# DLY-056-13V_3A-KP212.net
KiCad netlist of a schematic drawn in Altium Designer
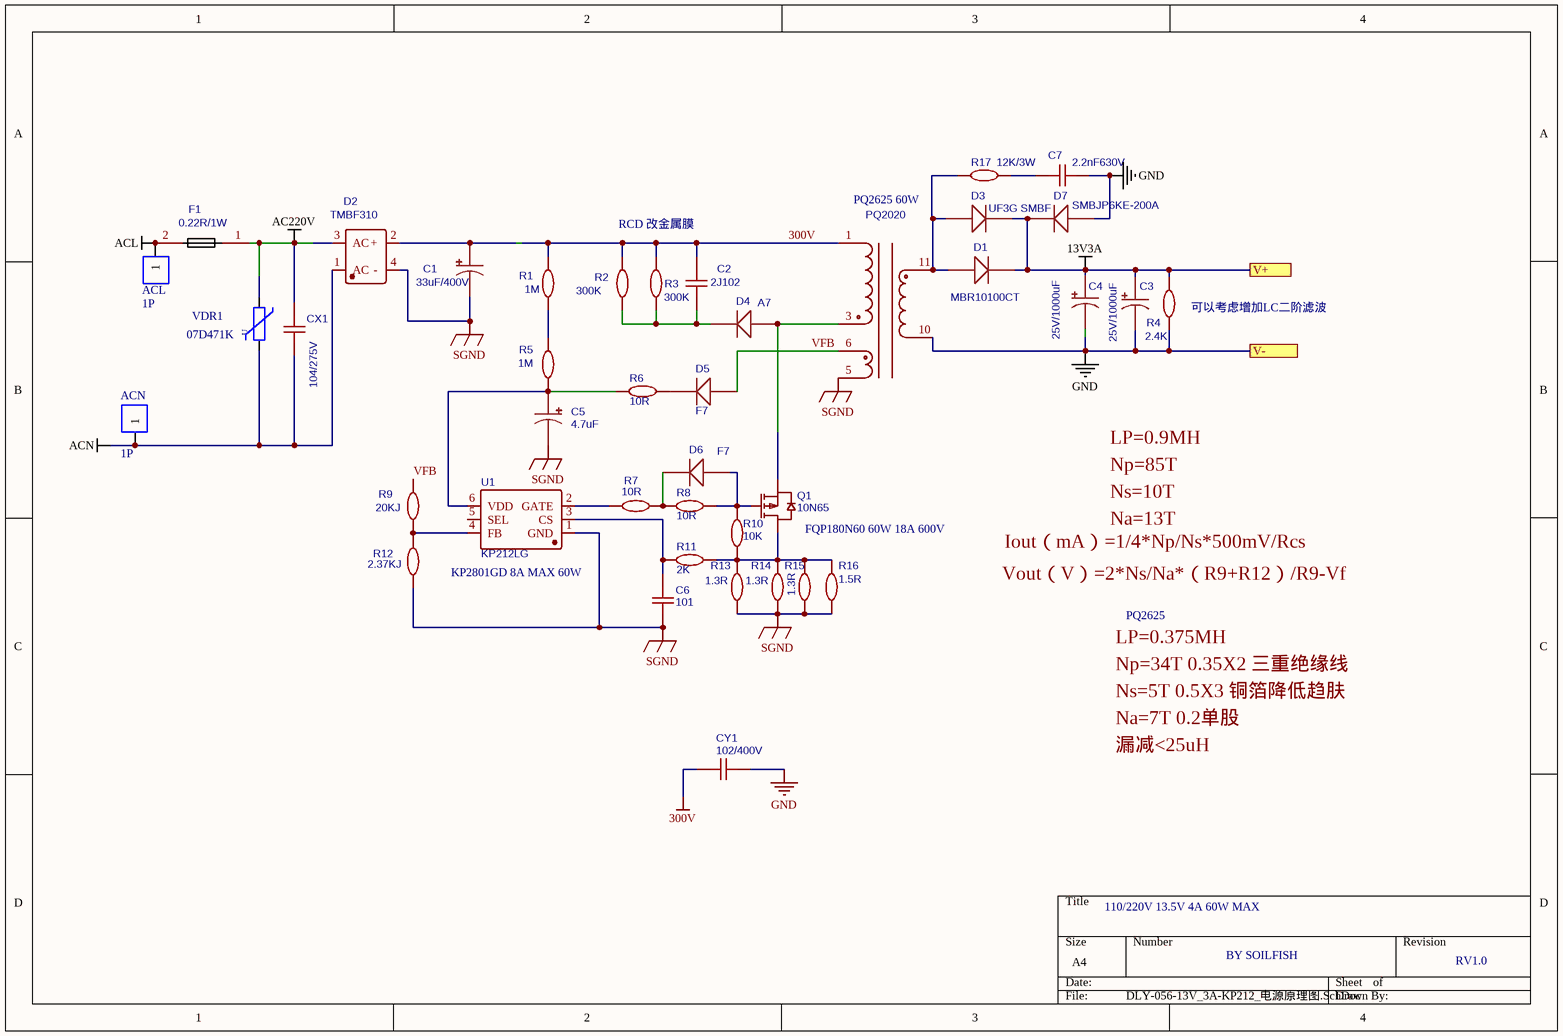
[diagram p0: DLY-056-13V_3A-KP212_电源原理图.SchDoc]

(export (version "E")
  (design (tool "Eeschema 10.0.6"))
  (components
    (comp (ref "ACL")
      (value "1P")
      (footprint "TEST3.0_top")
      (libsource (lib "KENNED 原理图标准封装-2023-9-7") (part "1P"))
    )
    (comp (ref "ACN")
      (value "1P")
      (footprint "TEST3.0_top")
      (libsource (lib "KENNED 原理图标准封装-2023-9-7") (part "1P"))
    )
    (comp (ref "C1")
      (value "33uF/400V")
      (footprint "DIP-EC5.0X12.5X20-A")
      (fields
        (field (name "BOM_SUPPLIER PART") "C503210")
        (field (name "BOM_MANUFACTURER PART") "01EC0069SHG4.7uF400V")
        (field (name "CONTRIBUTOR") "LCSC")
      )
      (libsource (lib "altium-import") (part "root_0_4.7uF_"))
    )
    (comp (ref "C2")
      (value "2J102")
      (footprint "SMT-1206C")
      (fields
        (field (name "BOM_MANUFACTURER PART") "CL10B104KA8NNNC")
        (field (name "BOM_SUPPLIER PART") "C1590")
      )
      (libsource (lib "altium-import") (part "root_1_102/400V_"))
    )
    (comp (ref "C3")
      (value "25V/1000uF")
      (footprint "DIP-EC3.5X8X11.5-A")
      (fields
        (field (name "BOM_SUPPLIER PART") "C503210")
        (field (name "BOM_MANUFACTURER PART") "01EC0069SHG4.7uF400V")
        (field (name "CONTRIBUTOR") "LCSC")
      )
      (libsource (lib "altium-import") (part "root_0_680uF_"))
    )
    (comp (ref "C4")
      (value "25V/1000uF")
      (footprint "DIP-EC3.5X8X11.5-A")
      (fields
        (field (name "BOM_SUPPLIER PART") "C503210")
        (field (name "BOM_MANUFACTURER PART") "01EC0069SHG4.7uF400V")
        (field (name "CONTRIBUTOR") "LCSC")
      )
      (libsource (lib "altium-import") (part "root_0_680uF_"))
    )
    (comp (ref "C5")
      (value "4.7uF")
      (footprint "DIP-EC2.5X5X11")
      (fields
        (field (name "BOM_SUPPLIER PART") "C503210")
        (field (name "BOM_MANUFACTURER PART") "01EC0069SHG4.7uF400V")
        (field (name "CONTRIBUTOR") "LCSC")
      )
      (libsource (lib "altium-import") (part "root_0_mirrored_4.7uF_"))
    )
    (comp (ref "C6")
      (value "101")
      (footprint "0805_C")
      (fields
        (field (name "BOM_MANUFACTURER PART") "CL10B104KA8NNNC")
        (field (name "BOM_SUPPLIER PART") "C1590")
      )
      (libsource (lib "altium-import") (part "root_1_102/400V_"))
    )
    (comp (ref "C7")
      (value "2.2nF630V")
      (footprint "SMT-1206C")
      (fields
        (field (name "BOM_MANUFACTURER PART") "CL10B104KA8NNNC")
        (field (name "BOM_SUPPLIER PART") "C1590")
      )
      (libsource (lib "altium-import") (part "root_2_102/400V_"))
    )
    (comp (ref "CX1")
      (value "104/275V")
      (footprint "AII-C10X5-5")
      (fields
        (field (name "BOM_MANUFACTURER PART") "CL10B104KA8NNNC")
        (field (name "BOM_SUPPLIER PART") "C1590")
      )
      (libsource (lib "altium-import") (part "root_1_102/400V_"))
    )
    (comp (ref "CY1")
      (value "102/400V")
      (footprint "MI-CY11.5X4.5-10")
      (fields
        (field (name "BOM_MANUFACTURER PART") "CL10B104KA8NNNC")
        (field (name "BOM_SUPPLIER PART") "C1590")
      )
      (libsource (lib "altium-import") (part "root_2_471/100V_"))
    )
    (comp (ref "D1")
      (value "MBR10100CT")
      (footprint "SMT-TO252锡膏-二极管")
      (fields
        (field (name "BOM_MANUFACTURER PART") "1N4148WSF-7")
        (field (name "BOM_SUPPLIER PART") "C119617")
        (field (name "CONTRIBUTOR") "LCSC")
      )
      (libsource (lib "altium-import") (part "root_2_A7_"))
    )
    (comp (ref "D2")
      (value "TMBF310")
      (footprint "DBS")
      (fields
        (field (name "BOM_SUPPLIER PART") "C347350")
        (field (name "BOM_MANUFACTURER PART") "MB10F(0.8A)")
        (field (name "CONTRIBUTOR") "LCSC")
      )
      (libsource (lib "altium-import") (part "root_1_MB10F(0.8A)_"))
    )
    (comp (ref "D3")
      (value "UF3G SMBF")
      (footprint "SMT-TO252锡膏-二极管")
      (fields
        (field (name "BOM_MANUFACTURER PART") "1N4148WSF-7")
        (field (name "BOM_SUPPLIER PART") "C119617")
        (field (name "CONTRIBUTOR") "LCSC")
      )
      (libsource (lib "altium-import") (part "root_2_A7_"))
    )
    (comp (ref "D4")
      (value "A7")
      (footprint "SMA(DO-214AC)_S1")
      (fields
        (field (name "BOM_MANUFACTURER PART") "1N4148WSF-7")
        (field (name "BOM_SUPPLIER PART") "C119617")
        (field (name "CONTRIBUTOR") "LCSC")
      )
      (libsource (lib "altium-import") (part "root_0_A7_"))
    )
    (comp (ref "D5")
      (value "F7")
      (footprint "SMT-SOD123锡膏")
      (fields
        (field (name "BOM_MANUFACTURER PART") "1N4148WSF-7")
        (field (name "BOM_SUPPLIER PART") "C119617")
        (field (name "CONTRIBUTOR") "LCSC")
      )
      (libsource (lib "altium-import") (part "root_2_mirrored_A7_"))
    )
    (comp (ref "D6")
      (value "F7")
      (footprint "SMT-SOD123锡膏")
      (fields
        (field (name "BOM_MANUFACTURER PART") "1N4148WSF-7")
        (field (name "BOM_SUPPLIER PART") "C119617")
        (field (name "CONTRIBUTOR") "LCSC")
      )
      (libsource (lib "altium-import") (part "root_0_A7_"))
    )
    (comp (ref "D7")
      (value "SMBJP6KE-200A")
      (footprint "SMT-TO252锡膏-二极管")
      (fields
        (field (name "BOM_MANUFACTURER PART") "1N4148WSF-7")
        (field (name "BOM_SUPPLIER PART") "C119617")
        (field (name "CONTRIBUTOR") "LCSC")
      )
      (libsource (lib "altium-import") (part "root_0_A7_"))
    )
    (comp (ref "F1")
      (value "0.22R/1W")
      (footprint "AI-R11X4-15")
      (fields (field (name "BOM_SUPPLIER PART") "C36902"))
      (libsource (lib "altium-import") (part "root_2_2A/250V_"))
    )
    (comp (ref "Q1")
      (value "10N65")
      (footprint "TO-220带散热片-MOS")
      (fields
        (field (name "BOM_SUPPLIER PART") "C239055")
        (field (name "BOM_MANUFACTURER PART") "3401")
        (field (name "CONTRIBUTOR") "LCSC")
      )
      (libsource (lib "altium-import") (part "root_2_3401_"))
    )
    (comp (ref "R1")
      (value "1M")
      (footprint "1206_r")
      (fields
        (field (name "BOM_SUPPLIER PART") "C270129")
        (field (name "BOM_MANUFACTURER PART") "RMC04024.7K1%N")
        (field (name "CONTRIBUTOR") "LCSC")
      )
      (libsource (lib "altium-import") (part "root_1_300K_"))
    )
    (comp (ref "R2")
      (value "300K")
      (footprint "1206_r")
      (fields
        (field (name "BOM_SUPPLIER PART") "C270129")
        (field (name "BOM_MANUFACTURER PART") "RMC04024.7K1%N")
        (field (name "CONTRIBUTOR") "LCSC")
      )
      (libsource (lib "altium-import") (part "root_1_120R_"))
    )
    (comp (ref "R3")
      (value "300K")
      (footprint "1206_r")
      (fields
        (field (name "BOM_SUPPLIER PART") "C270129")
        (field (name "BOM_MANUFACTURER PART") "RMC04024.7K1%N")
        (field (name "CONTRIBUTOR") "LCSC")
      )
      (libsource (lib "altium-import") (part "root_1_300K_"))
    )
    (comp (ref "R4")
      (value "2.4K")
      (footprint "0805_r")
      (fields
        (field (name "BOM_SUPPLIER PART") "C270129")
        (field (name "BOM_MANUFACTURER PART") "RMC04024.7K1%N")
        (field (name "CONTRIBUTOR") "LCSC")
      )
      (libsource (lib "altium-import") (part "root_3_6.8K_"))
    )
    (comp (ref "R5")
      (value "1M")
      (footprint "1206_r")
      (fields
        (field (name "BOM_SUPPLIER PART") "C270129")
        (field (name "BOM_MANUFACTURER PART") "RMC04024.7K1%N")
        (field (name "CONTRIBUTOR") "LCSC")
      )
      (libsource (lib "altium-import") (part "root_1_300K_"))
    )
    (comp (ref "R6")
      (value "10R")
      (footprint "0805_r")
      (fields
        (field (name "BOM_SUPPLIER PART") "C270129")
        (field (name "BOM_MANUFACTURER PART") "RMC04024.7K1%N")
        (field (name "CONTRIBUTOR") "LCSC")
      )
      (libsource (lib "altium-import") (part "root_0_mirrored_300K_"))
    )
    (comp (ref "R7")
      (value "10R")
      (footprint "0805_r")
      (fields
        (field (name "BOM_SUPPLIER PART") "C270129")
        (field (name "BOM_MANUFACTURER PART") "RMC04024.7K1%N")
        (field (name "CONTRIBUTOR") "LCSC")
      )
      (libsource (lib "altium-import") (part "root_2_300K_"))
    )
    (comp (ref "R8")
      (value "10R")
      (footprint "0805_r")
      (fields
        (field (name "BOM_SUPPLIER PART") "C270129")
        (field (name "BOM_MANUFACTURER PART") "RMC04024.7K1%N")
        (field (name "CONTRIBUTOR") "LCSC")
      )
      (libsource (lib "altium-import") (part "root_2_300K_"))
    )
    (comp (ref "R9")
      (value "20KJ")
      (footprint "0805_r")
      (fields
        (field (name "BOM_SUPPLIER PART") "C270129")
        (field (name "BOM_MANUFACTURER PART") "RMC04024.7K1%N")
        (field (name "CONTRIBUTOR") "LCSC")
      )
      (libsource (lib "altium-import") (part "root_3_300K_"))
    )
    (comp (ref "R10")
      (value "10K")
      (footprint "0805_r")
      (fields
        (field (name "BOM_SUPPLIER PART") "C270129")
        (field (name "BOM_MANUFACTURER PART") "RMC04024.7K1%N")
        (field (name "CONTRIBUTOR") "LCSC")
      )
      (libsource (lib "altium-import") (part "root_3_300K_"))
    )
    (comp (ref "R11")
      (value "2K")
      (footprint "0805_r")
      (fields
        (field (name "BOM_SUPPLIER PART") "C270129")
        (field (name "BOM_MANUFACTURER PART") "RMC04024.7K1%N")
        (field (name "CONTRIBUTOR") "LCSC")
      )
      (libsource (lib "altium-import") (part "root_2_300K_"))
    )
    (comp (ref "R12")
      (value "2.37KJ")
      (footprint "0805_r")
      (fields
        (field (name "BOM_SUPPLIER PART") "C270129")
        (field (name "BOM_MANUFACTURER PART") "RMC04024.7K1%N")
        (field (name "CONTRIBUTOR") "LCSC")
      )
      (libsource (lib "altium-import") (part "root_3_300K_"))
    )
    (comp (ref "R13")
      (value "1.3R")
      (footprint "SMT-1206")
      (fields
        (field (name "BOM_SUPPLIER PART") "C270129")
        (field (name "BOM_MANUFACTURER PART") "RMC04024.7K1%N")
        (field (name "CONTRIBUTOR") "LCSC")
      )
      (libsource (lib "altium-import") (part "root_1_10K_"))
    )
    (comp (ref "R14")
      (value "1.3R")
      (footprint "SMT-1206")
      (fields
        (field (name "BOM_SUPPLIER PART") "C270129")
        (field (name "BOM_MANUFACTURER PART") "RMC04024.7K1%N")
        (field (name "CONTRIBUTOR") "LCSC")
      )
      (libsource (lib "altium-import") (part "root_1_10K_"))
    )
    (comp (ref "R15")
      (value "1.3R")
      (footprint "SMT-1206")
      (fields
        (field (name "BOM_SUPPLIER PART") "C270129")
        (field (name "BOM_MANUFACTURER PART") "RMC04024.7K1%N")
        (field (name "CONTRIBUTOR") "LCSC")
      )
      (libsource (lib "altium-import") (part "root_1_10K_"))
    )
    (comp (ref "R16")
      (value "1.5R")
      (footprint "SMT-1206")
      (fields
        (field (name "BOM_SUPPLIER PART") "C270129")
        (field (name "BOM_MANUFACTURER PART") "RMC04024.7K1%N")
        (field (name "CONTRIBUTOR") "LCSC")
      )
      (libsource (lib "altium-import") (part "root_1_10K_"))
    )
    (comp (ref "R17")
      (value "12K/3W")
      (footprint "0805_r")
      (fields
        (field (name "BOM_SUPPLIER PART") "C270129")
        (field (name "BOM_MANUFACTURER PART") "RMC04024.7K1%N")
        (field (name "CONTRIBUTOR") "LCSC")
      )
      (libsource (lib "altium-import") (part "root_0_6.8K_"))
    )
    (comp (ref "T1")
      (value "PQ2020")
      (footprint "EC22-13-1")
      (fields (field (name "CONTRIBUTOR") "RICK-SHEN"))
      (libsource (lib "X40(7311)") (part "EFD2020"))
    )
    (comp (ref "U1")
      (value "KP212LG")
      (footprint "SOT-23-6")
      (fields (field (name "BOM_MANUFACTURER PART") "8205SS") (field (name "BOM_SUPPLIER PART") "C108055"))
      (libsource (lib "altium-import") (part "root_0_mirrored_HTX1820_"))
    )
    (comp (ref "VDR1")
      (value "07D471K")
      (footprint "MI-C7.5X5-5")
      (libsource (lib "KENNED 原理图标准封装-20170515") (part "ZNR"))
    )
  )
  (nets
    (net (code "1") (name "/VFB") (class "Default")
      (node (ref "D5") (pin "1") (pinfunction "A_1") (pintype "passive"))
      (node (ref "R9") (pin "1") (pinfunction "1_1") (pintype "passive"))
      (node (ref "T1") (pin "6") (pinfunction "4_6") (pintype "passive"))
    )
    (net (code "2") (name "13V3A") (class "Default")
      (node (ref "C3") (pin "1") (pinfunction "1_1") (pintype "passive"))
      (node (ref "C4") (pin "1") (pinfunction "1_1") (pintype "passive"))
      (node (ref "D1") (pin "2") (pinfunction "C_2") (pintype "passive"))
      (node (ref "D3") (pin "2") (pinfunction "C_2") (pintype "passive"))
      (node (ref "D7") (pin "2") (pinfunction "C_2") (pintype "passive"))
      (node (ref "R4") (pin "1") (pinfunction "1_1") (pintype "passive"))
    )
    (net (code "3") (name "300V") (class "Default")
      (node (ref "C1") (pin "1") (pinfunction "1_1") (pintype "passive"))
      (node (ref "C2") (pin "2") (pinfunction "2_2") (pintype "passive"))
      (node (ref "CY1") (pin "2") (pinfunction "2_2") (pintype "passive"))
      (node (ref "D2") (pin "2") (pinfunction "+_2") (pintype "passive"))
      (node (ref "R1") (pin "2") (pinfunction "2_2") (pintype "passive"))
      (node (ref "R2") (pin "2") (pinfunction "2_2") (pintype "passive"))
      (node (ref "R3") (pin "2") (pinfunction "2_2") (pintype "passive"))
      (node (ref "T1") (pin "1") (pinfunction "1_1") (pintype "passive"))
    )
    (net (code "4") (name "AC220V") (class "Default")
      (node (ref "CX1") (pin "2") (pinfunction "2_2") (pintype "passive"))
      (node (ref "D2") (pin "3") (pinfunction "AC_3") (pintype "passive"))
      (node (ref "F1") (pin "1") (pinfunction "1_1") (pintype "passive"))
      (node (ref "VDR1") (pin "2") (pinfunction "2_2") (pintype "passive"))
    )
    (net (code "5") (name "ACL") (class "Default")
      (node (ref "ACL") (pin "1") (pinfunction "1_1") (pintype "passive"))
      (node (ref "F1") (pin "2") (pinfunction "2_2") (pintype "passive"))
    )
    (net (code "6") (name "ACN") (class "Default")
      (node (ref "ACN") (pin "1") (pinfunction "1_1") (pintype "passive"))
      (node (ref "CX1") (pin "1") (pinfunction "1_1") (pintype "passive"))
      (node (ref "D2") (pin "1") (pinfunction "AC_1") (pintype "passive"))
      (node (ref "VDR1") (pin "1") (pinfunction "1_1") (pintype "passive"))
    )
    (net (code "7") (name "GND") (class "Default")
      (node (ref "C3") (pin "2") (pinfunction "2_2") (pintype "passive"))
      (node (ref "C4") (pin "2") (pinfunction "2_2") (pintype "passive"))
      (node (ref "C7") (pin "1") (pinfunction "1_1") (pintype "passive"))
      (node (ref "CY1") (pin "1") (pinfunction "1_1") (pintype "passive"))
      (node (ref "D7") (pin "1") (pinfunction "A_1") (pintype "passive"))
      (node (ref "R4") (pin "2") (pinfunction "2_2") (pintype "passive"))
      (node (ref "T1") (pin "10") (pinfunction "5_10") (pintype "passive"))
    )
    (net (code "8") (name "Net-(C7-Pad2)") (class "Default")
      (node (ref "C7") (pin "2") (pinfunction "2_2") (pintype "passive"))
      (node (ref "R17") (pin "2") (pinfunction "2_2") (pintype "passive"))
    )
    (net (code "9") (name "Net-(D1-A)") (class "Default")
      (node (ref "D1") (pin "1") (pinfunction "A_1") (pintype "passive"))
      (node (ref "D3") (pin "1") (pinfunction "A_1") (pintype "passive"))
      (node (ref "R17") (pin "1") (pinfunction "1_1") (pintype "passive"))
      (node (ref "T1") (pin "11") (pinfunction "8_11") (pintype "passive"))
    )
    (net (code "10") (name "Net-(D4-A)") (class "Default")
      (node (ref "D4") (pin "1") (pinfunction "A_1") (pintype "passive"))
      (node (ref "Q1") (pin "D") (pinfunction "D_D") (pintype "passive"))
      (node (ref "T1") (pin "3") (pinfunction "2_3") (pintype "passive"))
    )
    (net (code "11") (name "Net-(D4-C)") (class "Default")
      (node (ref "C2") (pin "1") (pinfunction "1_1") (pintype "passive"))
      (node (ref "D4") (pin "2") (pinfunction "C_2") (pintype "passive"))
      (node (ref "R2") (pin "1") (pinfunction "1_1") (pintype "passive"))
      (node (ref "R3") (pin "1") (pinfunction "1_1") (pintype "passive"))
    )
    (net (code "12") (name "Net-(D5-k)") (class "Default")
      (node (ref "D5") (pin "2") (pinfunction "k_2") (pintype "passive"))
      (node (ref "R6") (pin "1") (pinfunction "1_1") (pintype "passive"))
    )
    (net (code "13") (name "Net-(D6-A)") (class "Default")
      (node (ref "D6") (pin "1") (pinfunction "A_1") (pintype "passive"))
      (node (ref "Q1") (pin "G") (pinfunction "G_G") (pintype "passive"))
      (node (ref "R10") (pin "1") (pinfunction "1_1") (pintype "passive"))
      (node (ref "R8") (pin "1") (pinfunction "1_1") (pintype "passive"))
    )
    (net (code "14") (name "Net-(D6-C)") (class "Default")
      (node (ref "D6") (pin "2") (pinfunction "C_2") (pintype "passive"))
      (node (ref "R7") (pin "1") (pinfunction "1_1") (pintype "passive"))
      (node (ref "R8") (pin "2") (pinfunction "2_2") (pintype "passive"))
    )
    (net (code "15") (name "Net-(Q1-PadS)") (class "Default")
      (node (ref "Q1") (pin "S") (pinfunction "S_S") (pintype "passive"))
      (node (ref "R10") (pin "2") (pinfunction "2_2") (pintype "passive"))
      (node (ref "R11") (pin "1") (pinfunction "1_1") (pintype "passive"))
      (node (ref "R13") (pin "2") (pinfunction "2_2") (pintype "passive"))
      (node (ref "R14") (pin "2") (pinfunction "2_2") (pintype "passive"))
      (node (ref "R15") (pin "2") (pinfunction "2_2") (pintype "passive"))
      (node (ref "R16") (pin "2") (pinfunction "2_2") (pintype "passive"))
    )
    (net (code "16") (name "Net-(R1-Pad1)") (class "Default")
      (node (ref "R1") (pin "1") (pinfunction "1_1") (pintype "passive"))
      (node (ref "R5") (pin "2") (pinfunction "2_2") (pintype "passive"))
    )
    (net (code "17") (name "Net-(U1-CS)") (class "Default")
      (node (ref "C6") (pin "2") (pinfunction "2_2") (pintype "passive"))
      (node (ref "R11") (pin "2") (pinfunction "2_2") (pintype "passive"))
      (node (ref "U1") (pin "3") (pinfunction "CS_3") (pintype "passive"))
    )
    (net (code "18") (name "Net-(U1-FB)") (class "Default")
      (node (ref "R12") (pin "1") (pinfunction "1_1") (pintype "passive"))
      (node (ref "R9") (pin "2") (pinfunction "2_2") (pintype "passive"))
      (node (ref "U1") (pin "4") (pinfunction "FB_4") (pintype "passive"))
    )
    (net (code "19") (name "Net-(U1-GATE)") (class "Default")
      (node (ref "R7") (pin "2") (pinfunction "2_2") (pintype "passive"))
      (node (ref "U1") (pin "2") (pinfunction "GATE_2") (pintype "passive"))
    )
    (net (code "20") (name "Net-(U1-VDD)") (class "Default")
      (node (ref "C5") (pin "1") (pinfunction "1_1") (pintype "passive"))
      (node (ref "R5") (pin "1") (pinfunction "1_1") (pintype "passive"))
      (node (ref "R6") (pin "2") (pinfunction "2_2") (pintype "passive"))
      (node (ref "U1") (pin "6") (pinfunction "VDD_6") (pintype "passive"))
    )
    (net (code "21") (name "SGND") (class "Default")
      (node (ref "C1") (pin "2") (pinfunction "2_2") (pintype "passive"))
      (node (ref "C5") (pin "2") (pinfunction "2_2") (pintype "passive"))
      (node (ref "C6") (pin "1") (pinfunction "1_1") (pintype "passive"))
      (node (ref "D2") (pin "4") (pinfunction "-_4") (pintype "passive"))
      (node (ref "R12") (pin "2") (pinfunction "2_2") (pintype "passive"))
      (node (ref "R13") (pin "1") (pinfunction "1_1") (pintype "passive"))
      (node (ref "R14") (pin "1") (pinfunction "1_1") (pintype "passive"))
      (node (ref "R15") (pin "1") (pinfunction "1_1") (pintype "passive"))
      (node (ref "R16") (pin "1") (pinfunction "1_1") (pintype "passive"))
      (node (ref "T1") (pin "5") (pinfunction "3_5") (pintype "passive"))
      (node (ref "U1") (pin "1") (pinfunction "GND_1") (pintype "passive"))
    )
    (net (code "22") (name "unconnected-(U1-SEL-Pad5)") (class "Default")
      (node (ref "U1") (pin "5") (pinfunction "SEL_5") (pintype "passive"))
    )
  )
)
